# Fri3d_2026_CVR_00.net
KiCad netlist of a schematic drawn in Altium Designer
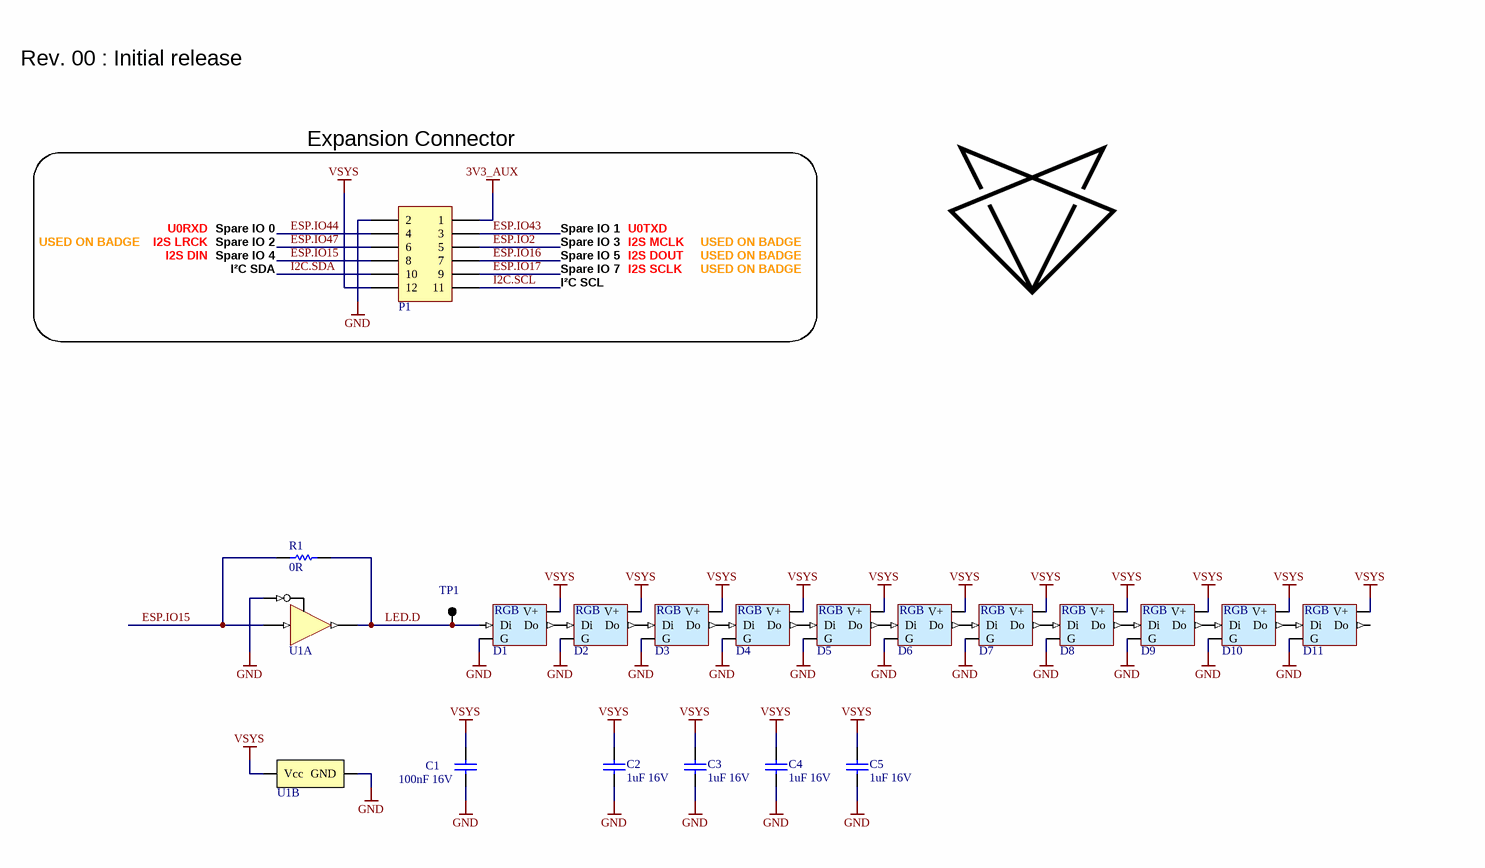
[diagram p0: Fri3d_2026_CVR_00.SchDoc]

(export (version "E")
  (design (tool "Eeschema 10.0.6"))
  (components
    (comp (ref "C1")
      (value "100nF 16V")
      (footprint "C0603_N")
      (description "Capacitor Ceramic")
      (libsource (lib "Phyx_Components") (part "CAP_CERAMIC"))
    )
    (comp (ref "C2")
      (value "1uF 16V")
      (footprint "C0603_N")
      (description "Capacitor Ceramic")
      (fields (field (name "Comment") "CAP_CERAMIC"))
      (libsource (lib "Phyx_Components") (part "CAP_CERAMIC"))
    )
    (comp (ref "C3")
      (value "1uF 16V")
      (footprint "C0603_N")
      (description "Capacitor Ceramic")
      (fields (field (name "Comment") "CAP_CERAMIC"))
      (libsource (lib "Phyx_Components") (part "CAP_CERAMIC"))
    )
    (comp (ref "C4")
      (value "1uF 16V")
      (footprint "C0603_N")
      (description "Capacitor Ceramic")
      (fields (field (name "Comment") "CAP_CERAMIC"))
      (libsource (lib "Phyx_Components") (part "CAP_CERAMIC"))
    )
    (comp (ref "C5")
      (value "1uF 16V")
      (footprint "C0603_N")
      (description "Capacitor Ceramic")
      (fields (field (name "Comment") "CAP_CERAMIC"))
      (libsource (lib "Phyx_Components") (part "CAP_CERAMIC"))
    )
    (comp (ref "D1")
      (value "WS2812 based digital RGB LED 4020 White package Side emitting")
      (footprint "LED_4020_WS2812B_WHITE")
      (description "=Description")
      (libsource (lib "Phyx_Components") (part "LED_RGB_WS2812B_4020"))
    )
    (comp (ref "D2")
      (value "WS2812 based digital RGB LED 4020 White package Side emitting")
      (footprint "LED_4020_WS2812B_WHITE")
      (description "=Description")
      (libsource (lib "Phyx_Components") (part "LED_RGB_WS2812B_4020"))
    )
    (comp (ref "D3")
      (value "WS2812 based digital RGB LED 4020 White package Side emitting")
      (footprint "LED_4020_WS2812B_WHITE")
      (description "=Description")
      (libsource (lib "Phyx_Components") (part "LED_RGB_WS2812B_4020"))
    )
    (comp (ref "D4")
      (value "WS2812 based digital RGB LED 4020 White package Side emitting")
      (footprint "LED_4020_WS2812B_WHITE")
      (description "=Description")
      (libsource (lib "Phyx_Components") (part "LED_RGB_WS2812B_4020"))
    )
    (comp (ref "D5")
      (value "WS2812 based digital RGB LED 4020 White package Side emitting")
      (footprint "LED_4020_WS2812B_WHITE")
      (description "=Description")
      (libsource (lib "Phyx_Components") (part "LED_RGB_WS2812B_4020"))
    )
    (comp (ref "D6")
      (value "WS2812 based digital RGB LED 4020 White package Side emitting")
      (footprint "LED_4020_WS2812B_WHITE")
      (description "=Description")
      (libsource (lib "Phyx_Components") (part "LED_RGB_WS2812B_4020"))
    )
    (comp (ref "D7")
      (value "WS2812 based digital RGB LED 4020 White package Side emitting")
      (footprint "LED_4020_WS2812B_WHITE")
      (description "=Description")
      (libsource (lib "Phyx_Components") (part "LED_RGB_WS2812B_4020"))
    )
    (comp (ref "D8")
      (value "WS2812 based digital RGB LED 4020 White package Side emitting")
      (footprint "LED_4020_WS2812B_WHITE")
      (description "=Description")
      (libsource (lib "Phyx_Components") (part "LED_RGB_WS2812B_4020"))
    )
    (comp (ref "D9")
      (value "WS2812 based digital RGB LED 4020 White package Side emitting")
      (footprint "LED_4020_WS2812B_WHITE")
      (description "=Description")
      (libsource (lib "Phyx_Components") (part "LED_RGB_WS2812B_4020"))
    )
    (comp (ref "D10")
      (value "WS2812 based digital RGB LED 4020 White package Side emitting")
      (footprint "LED_4020_WS2812B_WHITE")
      (description "=Description")
      (libsource (lib "Phyx_Components") (part "LED_RGB_WS2812B_4020"))
    )
    (comp (ref "D11")
      (value "WS2812 based digital RGB LED 4020 White package Side emitting")
      (footprint "LED_4020_WS2812B_WHITE")
      (description "=Description")
      (libsource (lib "Phyx_Components") (part "LED_RGB_WS2812B_4020"))
    )
    (comp (ref "P1")
      (value "Header 6X2")
      (footprint "HDR2X6")
      (libsource (lib "Phyx_Components") (part "Header 6X2"))
    )
    (comp (ref "R1")
      (value "0R")
      (footprint "R0402")
      (fields (field (name "Comment") "RESISTOR"))
      (libsource (lib "Phyx_Components") (part "RESISTOR"))
    )
    (comp (ref "TP1")
      (value "TEST_PAD")
      (footprint "TP_2x3mm")
      (libsource (lib "Phyx_Components") (part "TEST_PAD"))
    )
    (comp (ref "U1")
      (value "SN74AHCT1G125DCKR  Buffer, Tri-State, 4.5V to 5.5V")
      (footprint "TI_DCK_R-PDSO-G5")
      (description "=Description")
      (libsource (lib "Phyx_Components") (part "SN74AHCT1G125"))
    )
  )
  (nets
    (net (code "2") (name "/ESP.IO2") (class "Default")
      (node (ref "P1") (pin "5") (pinfunction "5_5") (pintype "passive"))
    )
    (net (code "3") (name "/ESP.IO15") (class "Default")
      (node (ref "P1") (pin "8") (pinfunction "8_8") (pintype "passive"))
      (node (ref "R1") (pin "2") (pinfunction "2_2") (pintype "passive"))
      (node (ref "U1") (pin "2") (pinfunction "A_2") (pintype "input"))
    )
    (net (code "4") (name "/ESP.IO16") (class "Default")
      (node (ref "P1") (pin "7") (pinfunction "7_7") (pintype "passive"))
    )
    (net (code "5") (name "/ESP.IO17") (class "Default")
      (node (ref "P1") (pin "9") (pinfunction "9_9") (pintype "passive"))
    )
    (net (code "6") (name "/ESP.IO43") (class "Default")
      (node (ref "P1") (pin "3") (pinfunction "3_3") (pintype "passive"))
    )
    (net (code "7") (name "/ESP.IO44") (class "Default")
      (node (ref "P1") (pin "4") (pinfunction "4_4") (pintype "passive"))
    )
    (net (code "8") (name "/ESP.IO47") (class "Default")
      (node (ref "P1") (pin "6") (pinfunction "6_6") (pintype "passive"))
    )
    (net (code "9") (name "/I2C.SCL") (class "Default")
      (node (ref "P1") (pin "11") (pinfunction "11_11") (pintype "passive"))
    )
    (net (code "10") (name "/I2C.SDA") (class "Default")
      (node (ref "P1") (pin "10") (pinfunction "10_10") (pintype "passive"))
    )
    (net (code "11") (name "/LED.D") (class "Default")
      (node (ref "D1") (pin "1") (pinfunction "Di_1") (pintype "input"))
      (node (ref "R1") (pin "1") (pinfunction "1_1") (pintype "passive"))
      (node (ref "TP1") (pin "1") (pinfunction "1_1") (pintype "passive"))
      (node (ref "U1") (pin "4") (pinfunction "Y_4") (pintype "output"))
    )
    (net (code "12") (name "3V3_AUX") (class "Default")
      (node (ref "P1") (pin "1") (pinfunction "1_1") (pintype "passive"))
    )
    (net (code "13") (name "GND") (class "Default")
      (node (ref "C1") (pin "2") (pinfunction "2_2") (pintype "passive"))
      (node (ref "C2") (pin "2") (pinfunction "2_2") (pintype "passive"))
      (node (ref "C3") (pin "2") (pinfunction "2_2") (pintype "passive"))
      (node (ref "C4") (pin "2") (pinfunction "2_2") (pintype "passive"))
      (node (ref "C5") (pin "2") (pinfunction "2_2") (pintype "passive"))
      (node (ref "D1") (pin "4") (pinfunction "G_4") (pintype "power_in"))
      (node (ref "D10") (pin "4") (pinfunction "G_4") (pintype "power_in"))
      (node (ref "D11") (pin "4") (pinfunction "G_4") (pintype "power_in"))
      (node (ref "D2") (pin "4") (pinfunction "G_4") (pintype "power_in"))
      (node (ref "D3") (pin "4") (pinfunction "G_4") (pintype "power_in"))
      (node (ref "D4") (pin "4") (pinfunction "G_4") (pintype "power_in"))
      (node (ref "D5") (pin "4") (pinfunction "G_4") (pintype "power_in"))
      (node (ref "D6") (pin "4") (pinfunction "G_4") (pintype "power_in"))
      (node (ref "D7") (pin "4") (pinfunction "G_4") (pintype "power_in"))
      (node (ref "D8") (pin "4") (pinfunction "G_4") (pintype "power_in"))
      (node (ref "D9") (pin "4") (pinfunction "G_4") (pintype "power_in"))
      (node (ref "P1") (pin "2") (pinfunction "2_2") (pintype "passive"))
      (node (ref "U1") (pin "1") (pinfunction "~{OE}_1") (pintype "input"))
      (node (ref "U1") (pin "3") (pinfunction "GND_3") (pintype "power_in"))
    )
    (net (code "14") (name "Net-(D1-Do)") (class "Default")
      (node (ref "D1") (pin "3") (pinfunction "Do_3") (pintype "output"))
      (node (ref "D2") (pin "1") (pinfunction "Di_1") (pintype "input"))
    )
    (net (code "15") (name "Net-(D2-Do)") (class "Default")
      (node (ref "D2") (pin "3") (pinfunction "Do_3") (pintype "output"))
      (node (ref "D3") (pin "1") (pinfunction "Di_1") (pintype "input"))
    )
    (net (code "16") (name "Net-(D3-Do)") (class "Default")
      (node (ref "D3") (pin "3") (pinfunction "Do_3") (pintype "output"))
      (node (ref "D4") (pin "1") (pinfunction "Di_1") (pintype "input"))
    )
    (net (code "17") (name "Net-(D4-Do)") (class "Default")
      (node (ref "D4") (pin "3") (pinfunction "Do_3") (pintype "output"))
      (node (ref "D5") (pin "1") (pinfunction "Di_1") (pintype "input"))
    )
    (net (code "18") (name "Net-(D5-Do)") (class "Default")
      (node (ref "D5") (pin "3") (pinfunction "Do_3") (pintype "output"))
      (node (ref "D6") (pin "1") (pinfunction "Di_1") (pintype "input"))
    )
    (net (code "19") (name "Net-(D6-Do)") (class "Default")
      (node (ref "D6") (pin "3") (pinfunction "Do_3") (pintype "output"))
      (node (ref "D7") (pin "1") (pinfunction "Di_1") (pintype "input"))
    )
    (net (code "20") (name "Net-(D7-Do)") (class "Default")
      (node (ref "D7") (pin "3") (pinfunction "Do_3") (pintype "output"))
      (node (ref "D8") (pin "1") (pinfunction "Di_1") (pintype "input"))
    )
    (net (code "21") (name "Net-(D8-Do)") (class "Default")
      (node (ref "D8") (pin "3") (pinfunction "Do_3") (pintype "output"))
      (node (ref "D9") (pin "1") (pinfunction "Di_1") (pintype "input"))
    )
    (net (code "22") (name "Net-(D10-Di)") (class "Default")
      (node (ref "D10") (pin "1") (pinfunction "Di_1") (pintype "input"))
      (node (ref "D9") (pin "3") (pinfunction "Do_3") (pintype "output"))
    )
    (net (code "23") (name "Net-(D10-Do)") (class "Default")
      (node (ref "D10") (pin "3") (pinfunction "Do_3") (pintype "output"))
      (node (ref "D11") (pin "1") (pinfunction "Di_1") (pintype "input"))
    )
    (net (code "24") (name "VSYS") (class "Default")
      (node (ref "C1") (pin "1") (pinfunction "1_1") (pintype "passive"))
      (node (ref "C2") (pin "1") (pinfunction "1_1") (pintype "passive"))
      (node (ref "C3") (pin "1") (pinfunction "1_1") (pintype "passive"))
      (node (ref "C4") (pin "1") (pinfunction "1_1") (pintype "passive"))
      (node (ref "C5") (pin "1") (pinfunction "1_1") (pintype "passive"))
      (node (ref "D1") (pin "2") (pinfunction "V+_2") (pintype "power_in"))
      (node (ref "D10") (pin "2") (pinfunction "V+_2") (pintype "power_in"))
      (node (ref "D11") (pin "2") (pinfunction "V+_2") (pintype "power_in"))
      (node (ref "D2") (pin "2") (pinfunction "V+_2") (pintype "power_in"))
      (node (ref "D3") (pin "2") (pinfunction "V+_2") (pintype "power_in"))
      (node (ref "D4") (pin "2") (pinfunction "V+_2") (pintype "power_in"))
      (node (ref "D5") (pin "2") (pinfunction "V+_2") (pintype "power_in"))
      (node (ref "D6") (pin "2") (pinfunction "V+_2") (pintype "power_in"))
      (node (ref "D7") (pin "2") (pinfunction "V+_2") (pintype "power_in"))
      (node (ref "D8") (pin "2") (pinfunction "V+_2") (pintype "power_in"))
      (node (ref "D9") (pin "2") (pinfunction "V+_2") (pintype "power_in"))
      (node (ref "P1") (pin "12") (pinfunction "12_12") (pintype "passive"))
      (node (ref "U1") (pin "5") (pinfunction "Vcc_5") (pintype "power_in"))
    )
    (net (code "25") (name "unconnected-(D11-Do-Pad3)") (class "Default")
      (node (ref "D11") (pin "3") (pinfunction "Do_3") (pintype "output"))
    )
  )
)
